# Touch_XPT2046.net
KiCad netlist of a schematic drawn in Altium Designer
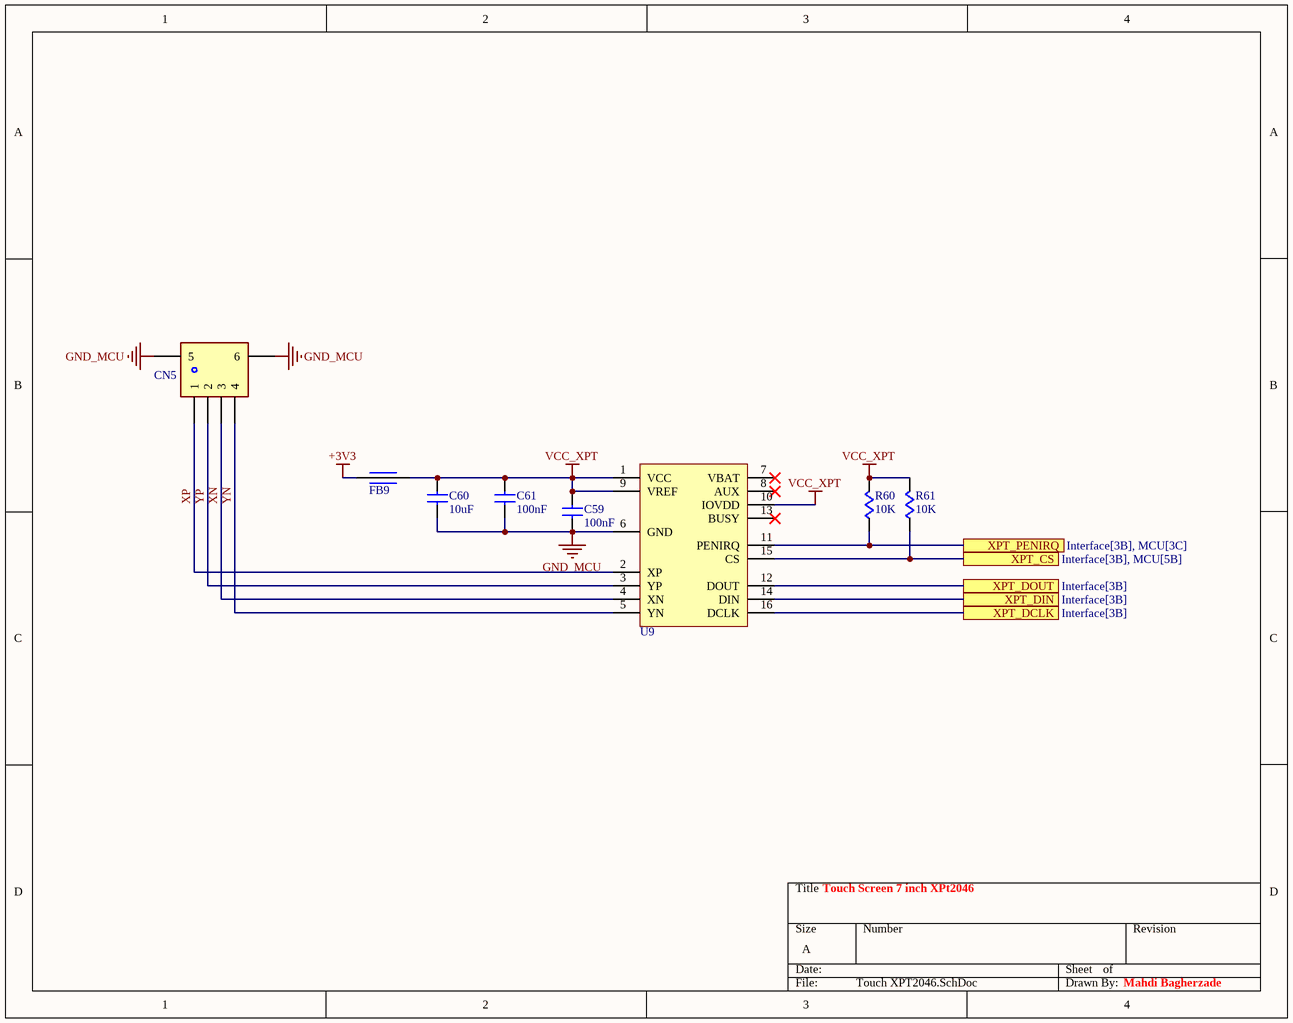
[diagram p0: Touch XPT2046.SchDoc]

(export (version "E")
  (design (tool "Eeschema 10.0.6"))
  (components
    (comp (ref "C59")
      (value "100nF")
      (footprint "C-0805")
      (description "CAPACITOR")
      (fields
        (field (name "VOLTAGE") "50V")
        (field (name "TOLERANCE") "X7R")
        (field (name "PUBLISHER") "Mahdi Bagherzadeh")
      )
      (libsource (lib "Mahdi-Bagherzadeh") (part "CAP-CER"))
    )
    (comp (ref "C60")
      (value "10uF")
      (footprint "C-0805")
      (description "CAPACITOR")
      (fields
        (field (name "VOLTAGE") "50V")
        (field (name "TOLERANCE") "X7R")
        (field (name "PUBLISHER") "Mahdi Bagherzadeh")
      )
      (libsource (lib "Mahdi-Bagherzadeh") (part "CAP-CER"))
    )
    (comp (ref "C61")
      (value "100nF")
      (footprint "C-0805")
      (description "CAPACITOR")
      (fields
        (field (name "VOLTAGE") "50V")
        (field (name "TOLERANCE") "X7R")
        (field (name "PUBLISHER") "Mahdi Bagherzadeh")
      )
      (libsource (lib "Mahdi-Bagherzadeh") (part "CAP-CER"))
    )
    (comp (ref "CN5")
      (value "Connector FPC Right-1mm-4 Pin")
      (footprint "CN-FPC-4-1mm-hor")
      (description "CONNECTOR")
      (fields (field (name "PUBLISHER") "Mahdi Bagherzadeh"))
      (libsource (lib "Mahdi-Bagherzadeh") (part "CN-FPC-4pin"))
    )
    (comp (ref "FB9")
      (value "Ferrite Bead SMD")
      (footprint "FB-0805")
      (description "INDUCATOR")
      (fields (field (name "PUBLISHER") "Mahdi Bagherzadeh"))
      (libsource (lib "Mahdi-Bagherzadeh") (part "FERRITE BEAD"))
    )
    (comp (ref "R60")
      (value "10K")
      (footprint "R-0805")
      (description "RESISTOR")
      (fields
        (field (name "POWER") "1/8W")
        (field (name "TOLERANCE") "5%")
        (field (name "PUBLISHER") "Mahdi Bagherzadeh")
      )
      (libsource (lib "Mahdi-Bagherzadeh") (part "RES"))
    )
    (comp (ref "R61")
      (value "10K")
      (footprint "R-0805")
      (description "RESISTOR")
      (fields
        (field (name "POWER") "1/8W")
        (field (name "TOLERANCE") "5%")
        (field (name "PUBLISHER") "Mahdi Bagherzadeh")
      )
      (libsource (lib "Mahdi-Bagherzadeh") (part "RES"))
    )
    (comp (ref "U9")
      (value "IC XPT2046-SMD")
      (footprint "TSSOP-16")
      (description "IC")
      (fields (field (name "PUBLISHER") "Mahdi Bagherzadeh"))
      (libsource (lib "Mahdi-Bagherzadeh") (part "XPT2046"))
    )
  )
  (nets
    (net (code "1") (name "+3V3") (class "Default")
      (node (ref "FB9") (pin "1") (pinfunction "1_1") (pintype "passive"))
    )
    (net (code "2") (name "/XN") (class "Default")
      (node (ref "CN5") (pin "3") (pinfunction "3_3") (pintype "passive"))
      (node (ref "U9") (pin "4") (pinfunction "XN_4") (pintype "passive"))
    )
    (net (code "3") (name "/XP") (class "Default")
      (node (ref "CN5") (pin "1") (pinfunction "1_1") (pintype "passive"))
      (node (ref "U9") (pin "2") (pinfunction "XP_2") (pintype "passive"))
    )
    (net (code "4") (name "/XPT_CS") (class "Default")
      (node (ref "R61") (pin "1") (pinfunction "1_1") (pintype "passive"))
      (node (ref "U9") (pin "15") (pinfunction "CS_15") (pintype "passive"))
    )
    (net (code "5") (name "/XPT_DCLK") (class "Default")
      (node (ref "U9") (pin "16") (pinfunction "DCLK_16") (pintype "passive"))
    )
    (net (code "6") (name "/XPT_DIN") (class "Default")
      (node (ref "U9") (pin "14") (pinfunction "DIN_14") (pintype "passive"))
    )
    (net (code "7") (name "/XPT_DOUT") (class "Default")
      (node (ref "U9") (pin "12") (pinfunction "DOUT_12") (pintype "passive"))
    )
    (net (code "8") (name "/XPT_PENIRQ") (class "Default")
      (node (ref "R60") (pin "1") (pinfunction "1_1") (pintype "passive"))
      (node (ref "U9") (pin "11") (pinfunction "PENIRQ_11") (pintype "passive"))
    )
    (net (code "9") (name "/YN") (class "Default")
      (node (ref "CN5") (pin "4") (pinfunction "4_4") (pintype "passive"))
      (node (ref "U9") (pin "5") (pinfunction "YN_5") (pintype "passive"))
    )
    (net (code "10") (name "/YP") (class "Default")
      (node (ref "CN5") (pin "2") (pinfunction "2_2") (pintype "passive"))
      (node (ref "U9") (pin "3") (pinfunction "YP_3") (pintype "passive"))
    )
    (net (code "11") (name "GND_MCU") (class "Default")
      (node (ref "C59") (pin "2") (pinfunction "2_2") (pintype "passive"))
      (node (ref "C60") (pin "2") (pinfunction "2_2") (pintype "passive"))
      (node (ref "C61") (pin "2") (pinfunction "2_2") (pintype "passive"))
      (node (ref "CN5") (pin "5") (pinfunction "5_5") (pintype "passive"))
      (node (ref "CN5") (pin "6") (pinfunction "6_6") (pintype "passive"))
      (node (ref "U9") (pin "6") (pinfunction "GND_6") (pintype "passive"))
    )
    (net (code "12") (name "VCC_XPT") (class "Default")
      (node (ref "C59") (pin "1") (pinfunction "1_1") (pintype "passive"))
      (node (ref "C60") (pin "1") (pinfunction "1_1") (pintype "passive"))
      (node (ref "C61") (pin "1") (pinfunction "1_1") (pintype "passive"))
      (node (ref "FB9") (pin "2") (pinfunction "2_2") (pintype "passive"))
      (node (ref "R60") (pin "2") (pinfunction "2_2") (pintype "passive"))
      (node (ref "R61") (pin "2") (pinfunction "2_2") (pintype "passive"))
      (node (ref "U9") (pin "1") (pinfunction "VCC_1") (pintype "passive"))
      (node (ref "U9") (pin "10") (pinfunction "IOVDD_10") (pintype "passive"))
      (node (ref "U9") (pin "9") (pinfunction "VREF_9") (pintype "passive"))
    )
    (net (code "13") (name "unconnected-(U9-AUX-Pad8)") (class "Default")
      (node (ref "U9") (pin "8") (pinfunction "AUX_8") (pintype "passive+no_connect"))
    )
    (net (code "14") (name "unconnected-(U9-BUSY-Pad13)") (class "Default")
      (node (ref "U9") (pin "13") (pinfunction "BUSY_13") (pintype "passive+no_connect"))
    )
    (net (code "15") (name "unconnected-(U9-VBAT-Pad7)") (class "Default")
      (node (ref "U9") (pin "7") (pinfunction "VBAT_7") (pintype "passive+no_connect"))
    )
  )
)
